# M3-LogicModule.net
KiCad netlist of a schematic drawn in EAGLE
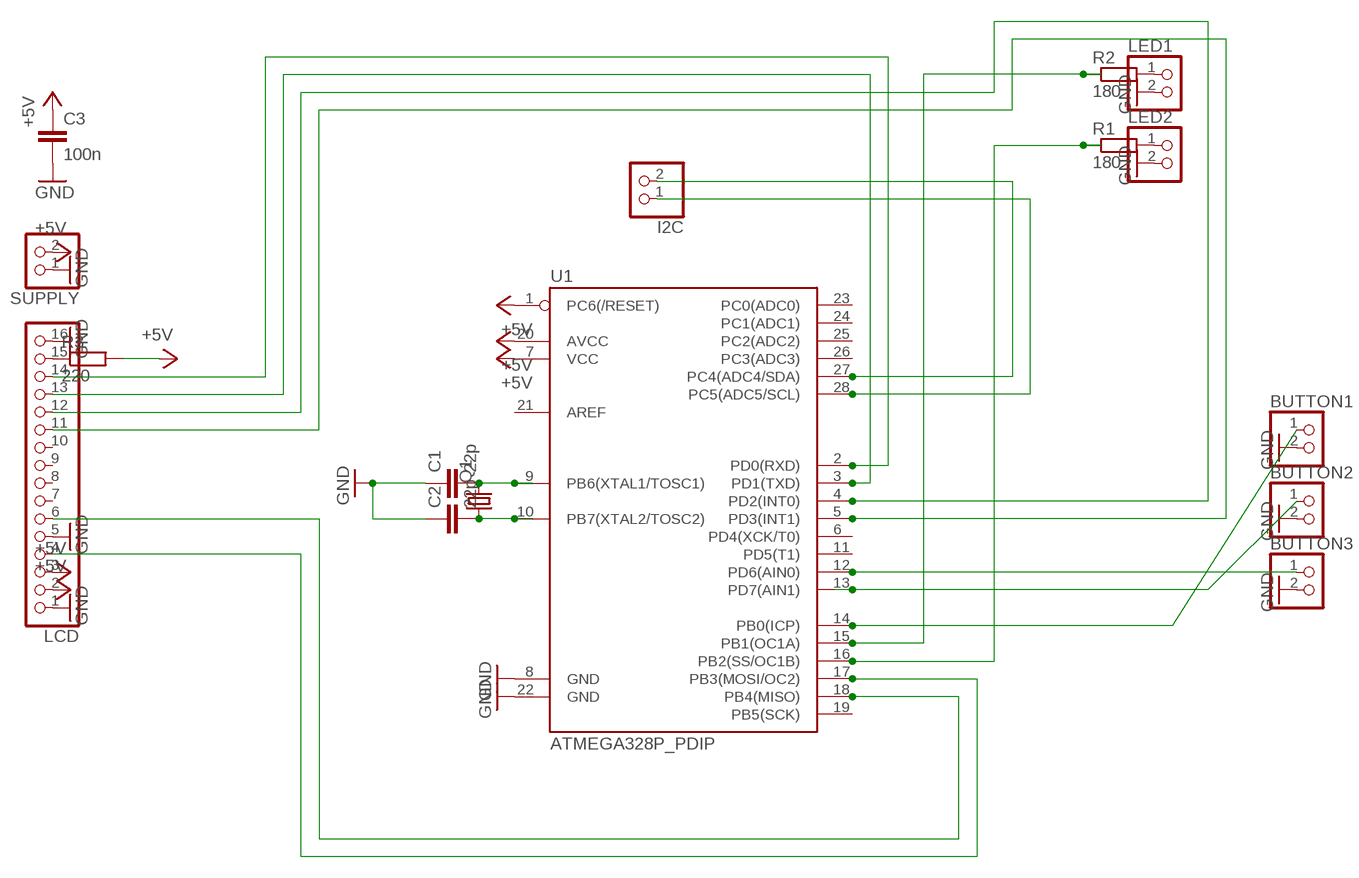
[diagram p0: schematic, sheet 1]

(export (version "E")
  (design (tool "Eeschema 10.0.6"))
  (components
    (comp (ref "BUTTON1")
      (value "PINHD-1X2")
      (footprint "eagle-import:1X02")
      (libsource (lib "eagle-import") (part "PINHD-1X2"))
    )
    (comp (ref "BUTTON2")
      (value "PINHD-1X2")
      (footprint "eagle-import:1X02")
      (libsource (lib "eagle-import") (part "PINHD-1X2"))
    )
    (comp (ref "BUTTON3")
      (value "PINHD-1X2")
      (footprint "eagle-import:1X02")
      (libsource (lib "eagle-import") (part "PINHD-1X2"))
    )
    (comp (ref "C1")
      (value "22p")
      (footprint "eagle-import:C025-025X050")
      (libsource (lib "eagle-import") (part "C-EU025-025X050"))
    )
    (comp (ref "C2")
      (value "22p")
      (footprint "eagle-import:C025-025X050")
      (libsource (lib "eagle-import") (part "C-EU025-025X050"))
    )
    (comp (ref "C3")
      (value "100n")
      (footprint "eagle-import:C2.5-3")
      (libsource (lib "eagle-import") (part "C2,5-3"))
    )
    (comp (ref "I2C")
      (value "PINHD-1X2")
      (footprint "eagle-import:1X02")
      (libsource (lib "eagle-import") (part "PINHD-1X2"))
    )
    (comp (ref "LCD")
      (value "PINHD-1X16")
      (footprint "eagle-import:1X16")
      (libsource (lib "eagle-import") (part "PINHD-1X16"))
    )
    (comp (ref "LED1")
      (value "PINHD-1X2")
      (footprint "eagle-import:1X02")
      (libsource (lib "eagle-import") (part "PINHD-1X2"))
    )
    (comp (ref "LED2")
      (value "PINHD-1X2")
      (footprint "eagle-import:1X02")
      (libsource (lib "eagle-import") (part "PINHD-1X2"))
    )
    (comp (ref "Q1")
      (value "CRYSTALHC49S")
      (footprint "eagle-import:HC49_S")
      (libsource (lib "eagle-import") (part "CRYSTALHC49S"))
    )
    (comp (ref "R1")
      (value "180")
      (footprint "eagle-import:0309_12")
      (libsource (lib "eagle-import") (part "resistor_R-EU_0309/12"))
    )
    (comp (ref "R2")
      (value "180")
      (footprint "eagle-import:0309_12")
      (libsource (lib "eagle-import") (part "resistor_R-EU_0309/12"))
    )
    (comp (ref "R3")
      (value "220")
      (footprint "eagle-import:0309_10")
      (libsource (lib "eagle-import") (part "R-EU_0309/10"))
    )
    (comp (ref "SUPPLY")
      (value "PINHD-1X2")
      (footprint "eagle-import:1X02")
      (libsource (lib "eagle-import") (part "PINHD-1X2"))
    )
    (comp (ref "U1")
      (value "ATMEGA328P_PDIP")
      (footprint "eagle-import:DIL28-3")
      (libsource (lib "eagle-import") (part "ATMEGA328P_PDIP"))
    )
  )
  (nets
    (net (code "1") (name "+5V") (class "Default")
      (node (ref "C3") (pin "1") (pinfunction "1_1") (pintype "passive"))
      (node (ref "LCD") (pin "2") (pinfunction "2_2") (pintype "passive"))
      (node (ref "LCD") (pin "3") (pinfunction "3_3") (pintype "passive"))
      (node (ref "R3") (pin "2") (pinfunction "2_2") (pintype "passive"))
      (node (ref "SUPPLY") (pin "2") (pinfunction "2_2") (pintype "passive"))
      (node (ref "U1") (pin "1") (pinfunction "PC6(/RESET)_1") (pintype "bidirectional"))
      (node (ref "U1") (pin "20") (pinfunction "AVCC_20") (pintype "bidirectional"))
      (node (ref "U1") (pin "7") (pinfunction "VCC_7") (pintype "bidirectional"))
    )
    (net (code "2") (name "GND") (class "Default")
      (node (ref "BUTTON1") (pin "2") (pinfunction "2_2") (pintype "passive"))
      (node (ref "BUTTON2") (pin "2") (pinfunction "2_2") (pintype "passive"))
      (node (ref "BUTTON3") (pin "2") (pinfunction "2_2") (pintype "passive"))
      (node (ref "C1") (pin "1") (pinfunction "1_1") (pintype "passive"))
      (node (ref "C2") (pin "1") (pinfunction "1_1") (pintype "passive"))
      (node (ref "C3") (pin "2") (pinfunction "2_2") (pintype "passive"))
      (node (ref "LCD") (pin "1") (pinfunction "1_1") (pintype "passive"))
      (node (ref "LCD") (pin "16") (pinfunction "16_16") (pintype "passive"))
      (node (ref "LCD") (pin "5") (pinfunction "5_5") (pintype "passive"))
      (node (ref "LED1") (pin "2") (pinfunction "2_2") (pintype "passive"))
      (node (ref "LED2") (pin "2") (pinfunction "2_2") (pintype "passive"))
      (node (ref "SUPPLY") (pin "1") (pinfunction "1_1") (pintype "passive"))
      (node (ref "U1") (pin "22") (pinfunction "GND_22") (pintype "bidirectional"))
      (node (ref "U1") (pin "8") (pinfunction "GND_8") (pintype "bidirectional"))
    )
    (net (code "3") (name "Net-(LCD-Pad15)") (class "Default")
      (node (ref "LCD") (pin "15") (pinfunction "15_15") (pintype "passive"))
      (node (ref "R3") (pin "1") (pinfunction "1_1") (pintype "passive"))
    )
    (net (code "4") (name "Net-(LED1-Pad1)") (class "Default")
      (node (ref "LED1") (pin "1") (pinfunction "1_1") (pintype "passive"))
      (node (ref "R2") (pin "2") (pinfunction "2_2") (pintype "passive"))
    )
    (net (code "5") (name "Net-(LED2-Pad1)") (class "Default")
      (node (ref "LED2") (pin "1") (pinfunction "1_1") (pintype "passive"))
      (node (ref "R1") (pin "2") (pinfunction "2_2") (pintype "passive"))
    )
    (net (code "6") (name "Net-(U1-PB0(ICP))") (class "Default")
      (node (ref "BUTTON1") (pin "1") (pinfunction "1_1") (pintype "passive"))
      (node (ref "U1") (pin "14") (pinfunction "PB0(ICP)_14") (pintype "bidirectional"))
    )
    (net (code "7") (name "Net-(U1-PB1(OC1A))") (class "Default")
      (node (ref "R2") (pin "1") (pinfunction "1_1") (pintype "passive"))
      (node (ref "U1") (pin "15") (pinfunction "PB1(OC1A)_15") (pintype "bidirectional"))
    )
    (net (code "8") (name "Net-(U1-PB2(SS{slash}OC1B))") (class "Default")
      (node (ref "R1") (pin "1") (pinfunction "1_1") (pintype "passive"))
      (node (ref "U1") (pin "16") (pinfunction "PB2(SS/OC1B)_16") (pintype "bidirectional"))
    )
    (net (code "9") (name "Net-(U1-PB3(MOSI{slash}OC2))") (class "Default")
      (node (ref "LCD") (pin "4") (pinfunction "4_4") (pintype "passive"))
      (node (ref "U1") (pin "17") (pinfunction "PB3(MOSI/OC2)_17") (pintype "bidirectional"))
    )
    (net (code "10") (name "Net-(U1-PB4(MISO))") (class "Default")
      (node (ref "LCD") (pin "6") (pinfunction "6_6") (pintype "passive"))
      (node (ref "U1") (pin "18") (pinfunction "PB4(MISO)_18") (pintype "bidirectional"))
    )
    (net (code "11") (name "Net-(U1-PB6(XTAL1{slash}TOSC1))") (class "Default")
      (node (ref "C1") (pin "2") (pinfunction "2_2") (pintype "passive"))
      (node (ref "Q1") (pin "2") (pinfunction "2_2") (pintype "passive"))
      (node (ref "U1") (pin "9") (pinfunction "PB6(XTAL1/TOSC1)_9") (pintype "bidirectional"))
    )
    (net (code "12") (name "Net-(U1-PB7(XTAL2{slash}TOSC2))") (class "Default")
      (node (ref "C2") (pin "2") (pinfunction "2_2") (pintype "passive"))
      (node (ref "Q1") (pin "1") (pinfunction "1_1") (pintype "passive"))
      (node (ref "U1") (pin "10") (pinfunction "PB7(XTAL2/TOSC2)_10") (pintype "bidirectional"))
    )
    (net (code "13") (name "Net-(U1-PC4(ADC4{slash}SDA))") (class "Default")
      (node (ref "I2C") (pin "2") (pinfunction "2_2") (pintype "passive"))
      (node (ref "U1") (pin "27") (pinfunction "PC4(ADC4/SDA)_27") (pintype "bidirectional"))
    )
    (net (code "14") (name "Net-(U1-PC5(ADC5{slash}SCL))") (class "Default")
      (node (ref "I2C") (pin "1") (pinfunction "1_1") (pintype "passive"))
      (node (ref "U1") (pin "28") (pinfunction "PC5(ADC5/SCL)_28") (pintype "bidirectional"))
    )
    (net (code "15") (name "Net-(U1-PD0(RXD))") (class "Default")
      (node (ref "LCD") (pin "14") (pinfunction "14_14") (pintype "passive"))
      (node (ref "U1") (pin "2") (pinfunction "PD0(RXD)_2") (pintype "bidirectional"))
    )
    (net (code "16") (name "Net-(U1-PD1(TXD))") (class "Default")
      (node (ref "LCD") (pin "13") (pinfunction "13_13") (pintype "passive"))
      (node (ref "U1") (pin "3") (pinfunction "PD1(TXD)_3") (pintype "bidirectional"))
    )
    (net (code "17") (name "Net-(U1-PD2(INT0))") (class "Default")
      (node (ref "LCD") (pin "12") (pinfunction "12_12") (pintype "passive"))
      (node (ref "U1") (pin "4") (pinfunction "PD2(INT0)_4") (pintype "bidirectional"))
    )
    (net (code "18") (name "Net-(U1-PD3(INT1))") (class "Default")
      (node (ref "LCD") (pin "11") (pinfunction "11_11") (pintype "passive"))
      (node (ref "U1") (pin "5") (pinfunction "PD3(INT1)_5") (pintype "bidirectional"))
    )
    (net (code "19") (name "Net-(U1-PD6(AIN0))") (class "Default")
      (node (ref "BUTTON3") (pin "1") (pinfunction "1_1") (pintype "passive"))
      (node (ref "U1") (pin "12") (pinfunction "PD6(AIN0)_12") (pintype "bidirectional"))
    )
    (net (code "20") (name "Net-(U1-PD7(AIN1))") (class "Default")
      (node (ref "BUTTON2") (pin "1") (pinfunction "1_1") (pintype "passive"))
      (node (ref "U1") (pin "13") (pinfunction "PD7(AIN1)_13") (pintype "bidirectional"))
    )
    (net (code "21") (name "unconnected-(LCD-Pad7)") (class "Default")
      (node (ref "LCD") (pin "7") (pinfunction "7_7") (pintype "passive"))
    )
    (net (code "22") (name "unconnected-(LCD-Pad8)") (class "Default")
      (node (ref "LCD") (pin "8") (pinfunction "8_8") (pintype "passive"))
    )
    (net (code "23") (name "unconnected-(LCD-Pad9)") (class "Default")
      (node (ref "LCD") (pin "9") (pinfunction "9_9") (pintype "passive"))
    )
    (net (code "24") (name "unconnected-(LCD-Pad10)") (class "Default")
      (node (ref "LCD") (pin "10") (pinfunction "10_10") (pintype "passive"))
    )
    (net (code "25") (name "unconnected-(U1-AREF-Pad21)") (class "Default")
      (node (ref "U1") (pin "21") (pinfunction "AREF_21") (pintype "bidirectional"))
    )
    (net (code "26") (name "unconnected-(U1-PB5(SCK)-Pad19)") (class "Default")
      (node (ref "U1") (pin "19") (pinfunction "PB5(SCK)_19") (pintype "bidirectional"))
    )
    (net (code "27") (name "unconnected-(U1-PC0(ADC0)-Pad23)") (class "Default")
      (node (ref "U1") (pin "23") (pinfunction "PC0(ADC0)_23") (pintype "bidirectional"))
    )
    (net (code "28") (name "unconnected-(U1-PC1(ADC1)-Pad24)") (class "Default")
      (node (ref "U1") (pin "24") (pinfunction "PC1(ADC1)_24") (pintype "bidirectional"))
    )
    (net (code "29") (name "unconnected-(U1-PC2(ADC2)-Pad25)") (class "Default")
      (node (ref "U1") (pin "25") (pinfunction "PC2(ADC2)_25") (pintype "bidirectional"))
    )
    (net (code "30") (name "unconnected-(U1-PC3(ADC3)-Pad26)") (class "Default")
      (node (ref "U1") (pin "26") (pinfunction "PC3(ADC3)_26") (pintype "bidirectional"))
    )
    (net (code "31") (name "unconnected-(U1-PD4(XCK{slash}T0)-Pad6)") (class "Default")
      (node (ref "U1") (pin "6") (pinfunction "PD4(XCK/T0)_6") (pintype "bidirectional"))
    )
    (net (code "32") (name "unconnected-(U1-PD5(T1)-Pad11)") (class "Default")
      (node (ref "U1") (pin "11") (pinfunction "PD5(T1)_11") (pintype "bidirectional"))
    )
  )
)
